# edl_transmitter.net
KiCad netlist of a schematic drawn in EAGLE
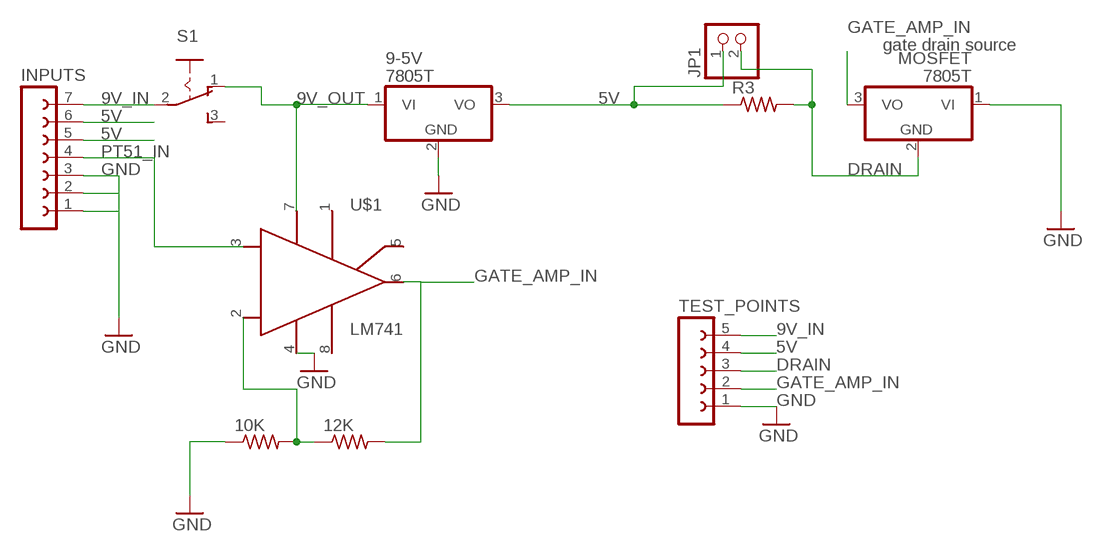
[diagram p0: schematic, sheet 1]

(export (version "E")
  (design (tool "Eeschema 10.0.6"))
  (components
    (comp (ref "9-5V")
      (value "7805T")
      (footprint "eagle-import:TO220H")
      (libsource (lib "eagle-import") (part "78T05"))
    )
    (comp (ref "10K")
      (value "R-US_0207/10")
      (footprint "eagle-import:0207_10")
      (libsource (lib "eagle-import") (part "R-US_0207/10"))
    )
    (comp (ref "12K")
      (value "R-US_0207/10")
      (footprint "eagle-import:0207_10")
      (libsource (lib "eagle-import") (part "R-US_0207/10"))
    )
    (comp (ref "INPUTS")
      (value "FE07-1")
      (footprint "eagle-import:FE07")
      (libsource (lib "eagle-import") (part "FE07-1"))
    )
    (comp (ref "JP1")
      (value "PINHD-1X2")
      (footprint "eagle-import:1X02")
      (libsource (lib "eagle-import") (part "PINHD-1X2"))
    )
    (comp (ref "MOSFET")
      (value "7805T")
      (footprint "eagle-import:TO220H")
      (libsource (lib "eagle-import") (part "78T05"))
    )
    (comp (ref "R3")
      (value "R-US_0207/10")
      (footprint "eagle-import:0207_10")
      (libsource (lib "eagle-import") (part "R-US_0207/10"))
    )
    (comp (ref "S1")
      (value "255SB")
      (footprint "eagle-import:255SB")
      (libsource (lib "eagle-import") (part "255SB"))
    )
    (comp (ref "TEST_POINTS")
      (value "FE05-1")
      (footprint "eagle-import:FE05-1")
      (libsource (lib "eagle-import") (part "FE05-1"))
    )
    (comp (ref "U$1")
      (value "OPAMP-741-DIP")
      (footprint "eagle-import:OPAMP-741-DIP")
      (libsource (lib "eagle-import") (part "OPAMP-741-DIP"))
    )
  )
  (nets
    (net (code "1") (name "/5V") (class "Default")
      (node (ref "9-5V") (pin "3") (pinfunction "VO_3") (pintype "passive"))
      (node (ref "INPUTS") (pin "5") (pinfunction "5_5") (pintype "passive"))
      (node (ref "INPUTS") (pin "6") (pinfunction "6_6") (pintype "passive"))
      (node (ref "JP1") (pin "1") (pinfunction "1_1") (pintype "passive"))
      (node (ref "R3") (pin "1") (pinfunction "1_1") (pintype "passive"))
      (node (ref "TEST_POINTS") (pin "4") (pinfunction "4_4") (pintype "passive"))
    )
    (net (code "2") (name "/9V_IN") (class "Default")
      (node (ref "INPUTS") (pin "7") (pinfunction "7_7") (pintype "passive"))
      (node (ref "S1") (pin "2") (pinfunction "P_2") (pintype "passive"))
      (node (ref "TEST_POINTS") (pin "5") (pinfunction "5_5") (pintype "passive"))
    )
    (net (code "3") (name "/9V_OUT") (class "Default")
      (node (ref "9-5V") (pin "1") (pinfunction "VI_1") (pintype "input"))
      (node (ref "S1") (pin "1") (pinfunction "O_1") (pintype "passive"))
      (node (ref "U$1") (pin "7") (pinfunction "7_7") (pintype "bidirectional"))
    )
    (net (code "4") (name "/DRAIN") (class "Default")
      (node (ref "JP1") (pin "2") (pinfunction "2_2") (pintype "passive"))
      (node (ref "MOSFET") (pin "2") (pinfunction "GND_2") (pintype "passive"))
      (node (ref "R3") (pin "2") (pinfunction "2_2") (pintype "passive"))
      (node (ref "TEST_POINTS") (pin "3") (pinfunction "3_3") (pintype "passive"))
    )
    (net (code "5") (name "/GATE_AMP_IN") (class "Default")
      (node (ref "12K") (pin "2") (pinfunction "2_2") (pintype "passive"))
      (node (ref "MOSFET") (pin "3") (pinfunction "VO_3") (pintype "passive"))
      (node (ref "TEST_POINTS") (pin "2") (pinfunction "2_2") (pintype "passive"))
      (node (ref "U$1") (pin "6") (pinfunction "6_6") (pintype "bidirectional"))
    )
    (net (code "6") (name "/PT51_IN") (class "Default")
      (node (ref "INPUTS") (pin "4") (pinfunction "4_4") (pintype "passive"))
      (node (ref "U$1") (pin "3") (pinfunction "3_3") (pintype "bidirectional"))
    )
    (net (code "7") (name "GND") (class "Default")
      (node (ref "10K") (pin "1") (pinfunction "1_1") (pintype "passive"))
      (node (ref "9-5V") (pin "2") (pinfunction "GND_2") (pintype "passive"))
      (node (ref "INPUTS") (pin "1") (pinfunction "1_1") (pintype "passive"))
      (node (ref "INPUTS") (pin "2") (pinfunction "2_2") (pintype "passive"))
      (node (ref "INPUTS") (pin "3") (pinfunction "3_3") (pintype "passive"))
      (node (ref "MOSFET") (pin "1") (pinfunction "VI_1") (pintype "input"))
      (node (ref "TEST_POINTS") (pin "1") (pinfunction "1_1") (pintype "passive"))
      (node (ref "U$1") (pin "4") (pinfunction "4_4") (pintype "bidirectional"))
    )
    (net (code "8") (name "Net-(10K-Pad2)") (class "Default")
      (node (ref "10K") (pin "2") (pinfunction "2_2") (pintype "passive"))
      (node (ref "12K") (pin "1") (pinfunction "1_1") (pintype "passive"))
      (node (ref "U$1") (pin "2") (pinfunction "2_2") (pintype "bidirectional"))
    )
    (net (code "9") (name "unconnected-(S1-S-Pad3)") (class "Default")
      (node (ref "S1") (pin "3") (pinfunction "S_3") (pintype "passive"))
    )
    (net (code "10") (name "unconnected-(U$1-Pad1)") (class "Default")
      (node (ref "U$1") (pin "1") (pinfunction "1_1") (pintype "bidirectional"))
    )
    (net (code "11") (name "unconnected-(U$1-Pad5)") (class "Default")
      (node (ref "U$1") (pin "5") (pinfunction "5_5") (pintype "bidirectional"))
    )
    (net (code "12") (name "unconnected-(U$1-Pad8)") (class "Default")
      (node (ref "U$1") (pin "8") (pinfunction "8_8") (pintype "bidirectional"))
    )
  )
)
